# BMS-S02-V01-CellMonitor.net
KiCad netlist of a schematic drawn in Altium Designer
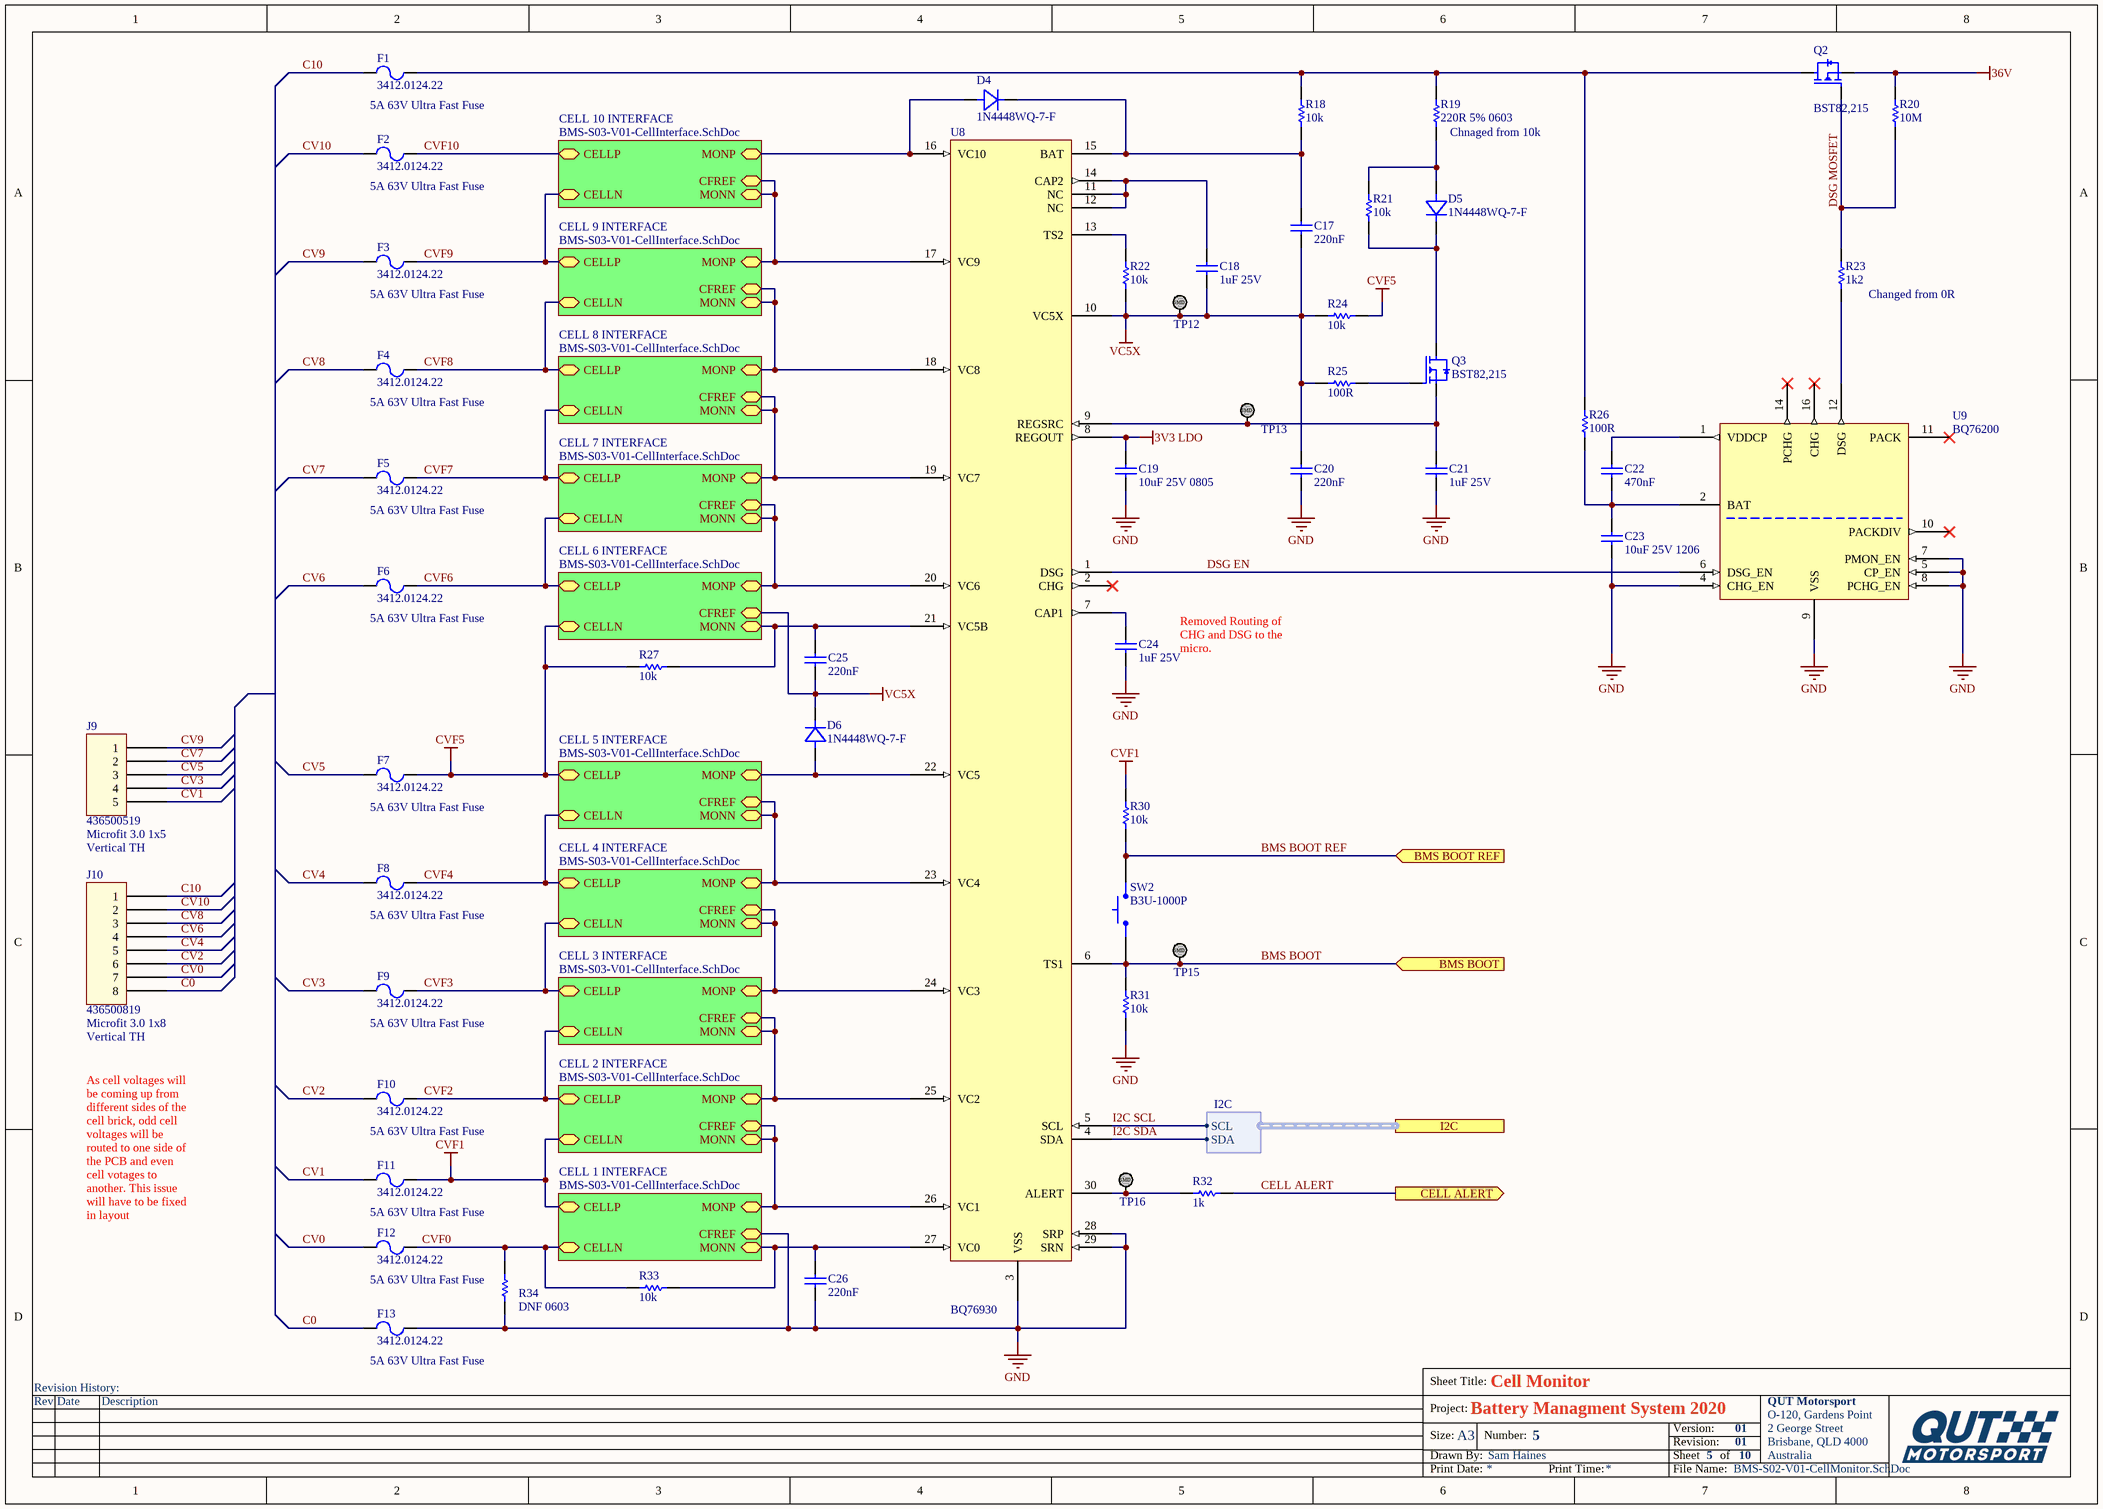
[diagram p0: BMS-S02-V01-CellMonitor.SchDoc]

(export (version "E")
  (design (tool "Eeschema 10.0.6"))
  (components
    (comp (ref "C17")
      (value "220nF")
      (footprint "Cap_Ceramic_0603")
      (description "Capacitor, Ceramic, SMD, 220nF, 50V, 5%, X7R, 0603")
      (libsource (lib "StandardCapacitors") (part "220nF 50V 5% X7R 0603"))
    )
    (comp (ref "C18")
      (value "1uF 25V")
      (footprint "Cap_Ceramic_0603")
      (description "Capacitor, Ceramic, SMD, 1uF, 25V, 5%, X7R, 0603")
      (libsource (lib "StandardCapacitors") (part "1uF 25V 5% X7R 0603"))
    )
    (comp (ref "C19")
      (value "10uF 25V 0805")
      (footprint "Cap_Ceramic_0805")
      (description "Capacitor, Ceramic, SMD, 10uF, 25V, 5%, X7R, 0805")
      (libsource (lib "StandardCapacitors") (part "10uF 25V 5% X7R 0805_1"))
    )
    (comp (ref "C20")
      (value "220nF")
      (footprint "Cap_Ceramic_0603")
      (description "Capacitor, Ceramic, SMD, 220nF, 50V, 5%, X7R, 0603")
      (libsource (lib "StandardCapacitors") (part "220nF 50V 5% X7R 0603"))
    )
    (comp (ref "C21")
      (value "1uF 25V")
      (footprint "Cap_Ceramic_0603")
      (description "Capacitor, Ceramic, SMD, 1uF, 25V, 5%, X7R, 0603")
      (libsource (lib "StandardCapacitors") (part "1uF 25V 5% X7R 0603"))
    )
    (comp (ref "C22")
      (value "470nF")
      (footprint "Cap_Ceramic_0603")
      (description "Capacitor, Ceramic, SMD, 470nF, 50V, 5%, X7R, 0603")
      (libsource (lib "StandardCapacitors") (part "470nF 50V 5% X7R 0603"))
    )
    (comp (ref "C23")
      (value "10uF 25V 1206")
      (footprint "Cap_Ceramic_1206")
      (description "Capacitor, Ceramic, SMD, 10uF, 25V, 10%, X7R, 1206")
      (libsource (lib "StandardCapacitors") (part "10uF 25V 10% X7R 1206"))
    )
    (comp (ref "C24")
      (value "1uF 25V")
      (footprint "Cap_Ceramic_0603")
      (description "Capacitor, Ceramic, SMD, 1uF, 25V, 5%, X7R, 0603")
      (libsource (lib "StandardCapacitors") (part "1uF 25V 5% X7R 0603"))
    )
    (comp (ref "C25")
      (value "220nF")
      (footprint "Cap_Ceramic_0603")
      (description "Capacitor, Ceramic, SMD, 220nF, 50V, 5%, X7R, 0603")
      (libsource (lib "StandardCapacitors") (part "220nF 50V 5% X7R 0603"))
    )
    (comp (ref "C26")
      (value "220nF")
      (footprint "Cap_Ceramic_0603")
      (description "Capacitor, Ceramic, SMD, 220nF, 50V, 5%, X7R, 0603")
      (libsource (lib "StandardCapacitors") (part "220nF 50V 5% X7R 0603"))
    )
    (comp (ref "D4")
      (value "1N4448WQ-7-F")
      (footprint "SMA")
      (description "Diode, SMD, 75V, 5%, 250mA, SOD123")
      (fields
        (field (name "MANUFACTURER") "ON Semiconductor / Fairchild")
        (field (name "MANUFACTURER PART NUMBER") "1N914BWS")
      )
      (libsource (lib "QUTMS_DiodeLibrary") (part "1N4448WQ-7-F"))
    )
    (comp (ref "D5")
      (value "1N4448WQ-7-F")
      (footprint "SMA")
      (description "Diode, SMD, 75V, 5%, 250mA, SOD123")
      (fields
        (field (name "MANUFACTURER") "ON Semiconductor / Fairchild")
        (field (name "MANUFACTURER PART NUMBER") "1N914BWS")
      )
      (libsource (lib "QUTMS_DiodeLibrary") (part "1N4448WQ-7-F"))
    )
    (comp (ref "D6")
      (value "1N4448WQ-7-F")
      (footprint "SMA")
      (description "Diode, SMD, 75V, 5%, 250mA, SOD123")
      (fields
        (field (name "MANUFACTURER") "ON Semiconductor / Fairchild")
        (field (name "MANUFACTURER PART NUMBER") "1N914BWS")
      )
      (libsource (lib "QUTMS_DiodeLibrary") (part "1N4448WQ-7-F"))
    )
    (comp (ref "F1")
      (value "3412.0124.22")
      (footprint "3412.0124.22")
      (description "FUSE BOARD MOUNT 5A 63VDC 0603")
      (libsource (lib "CellMonitor") (part "3412.0124.22"))
    )
    (comp (ref "F2")
      (value "3412.0124.22")
      (footprint "3412.0124.22")
      (description "FUSE BOARD MOUNT 5A 63VDC 0603")
      (libsource (lib "CellMonitor") (part "3412.0124.22"))
    )
    (comp (ref "F3")
      (value "3412.0124.22")
      (footprint "3412.0124.22")
      (description "FUSE BOARD MOUNT 5A 63VDC 0603")
      (libsource (lib "CellMonitor") (part "3412.0124.22"))
    )
    (comp (ref "F4")
      (value "3412.0124.22")
      (footprint "3412.0124.22")
      (description "FUSE BOARD MOUNT 5A 63VDC 0603")
      (libsource (lib "CellMonitor") (part "3412.0124.22"))
    )
    (comp (ref "F5")
      (value "3412.0124.22")
      (footprint "3412.0124.22")
      (description "FUSE BOARD MOUNT 5A 63VDC 0603")
      (libsource (lib "CellMonitor") (part "3412.0124.22"))
    )
    (comp (ref "F6")
      (value "3412.0124.22")
      (footprint "3412.0124.22")
      (description "FUSE BOARD MOUNT 5A 63VDC 0603")
      (libsource (lib "CellMonitor") (part "3412.0124.22"))
    )
    (comp (ref "F7")
      (value "3412.0124.22")
      (footprint "3412.0124.22")
      (description "FUSE BOARD MOUNT 5A 63VDC 0603")
      (libsource (lib "CellMonitor") (part "3412.0124.22"))
    )
    (comp (ref "F8")
      (value "3412.0124.22")
      (footprint "3412.0124.22")
      (description "FUSE BOARD MOUNT 5A 63VDC 0603")
      (libsource (lib "CellMonitor") (part "3412.0124.22"))
    )
    (comp (ref "F9")
      (value "3412.0124.22")
      (footprint "3412.0124.22")
      (description "FUSE BOARD MOUNT 5A 63VDC 0603")
      (libsource (lib "CellMonitor") (part "3412.0124.22"))
    )
    (comp (ref "F10")
      (value "3412.0124.22")
      (footprint "3412.0124.22")
      (description "FUSE BOARD MOUNT 5A 63VDC 0603")
      (libsource (lib "CellMonitor") (part "3412.0124.22"))
    )
    (comp (ref "F11")
      (value "3412.0124.22")
      (footprint "3412.0124.22")
      (description "FUSE BOARD MOUNT 5A 63VDC 0603")
      (libsource (lib "CellMonitor") (part "3412.0124.22"))
    )
    (comp (ref "F12")
      (value "3412.0124.22")
      (footprint "3412.0124.22")
      (description "FUSE BOARD MOUNT 5A 63VDC 0603")
      (libsource (lib "CellMonitor") (part "3412.0124.22"))
    )
    (comp (ref "F13")
      (value "3412.0124.22")
      (footprint "3412.0124.22")
      (description "FUSE BOARD MOUNT 5A 63VDC 0603")
      (libsource (lib "CellMonitor") (part "3412.0124.22"))
    )
    (comp (ref "J9")
      (value "436500519")
      (footprint "Microfit_1X5_V_TH")
      (libsource (lib "QUTMS_MicrofitLibrary") (part "Microfit_1x5"))
    )
    (comp (ref "J10")
      (value "436500819")
      (footprint "Microfit_1X8_V_TH")
      (libsource (lib "QUTMS_MicrofitLibrary") (part "Microfit_1x8"))
    )
    (comp (ref "Q2")
      (value "BST82,215")
      (footprint "BST82,215")
      (description "MOSFET N-CH, 20V, SOT23\r\nAlternate Part\r\n2N7002LT1G0SCT-ND")
      (libsource (lib "") (part "BST82,215_1"))
    )
    (comp (ref "Q3")
      (value "BST82,215")
      (footprint "BST82,215")
      (description "MOSFET N-CH, 20V, SOT23")
      (libsource (lib "CellMonitor") (part "BST82,215"))
    )
    (comp (ref "R18")
      (value "10k")
      (footprint "Res_ThinFilm_0603")
      (description "Resistor, SMD, 10k, 0.1W, 5%, 0603")
      (libsource (lib "StandardResistors") (part "10k 5% 0603"))
    )
    (comp (ref "R19")
      (value "220R 5% 0603")
      (footprint "Res_ThinFilm_0603")
      (description "Resistor, SMD, 220R, 0.1W, 5%, 0603")
      (libsource (lib "StandardResistors") (part "470R 5% 0603"))
    )
    (comp (ref "R20")
      (value "10M")
      (footprint "Res_ThinFilm_0603")
      (description "Resistor, SMD, 10M, 0.1W, 5%, 0603")
      (libsource (lib "StandardResistors") (part "10M 5% 0603"))
    )
    (comp (ref "R21")
      (value "10k")
      (footprint "Res_ThinFilm_0603")
      (description "Resistor, SMD, 10k, 0.1W, 5%, 0603")
      (libsource (lib "StandardResistors") (part "10k 5% 0603"))
    )
    (comp (ref "R22")
      (value "10k")
      (footprint "Res_ThinFilm_0603")
      (description "Resistor, SMD, 10k, 0.1W, 5%, 0603")
      (libsource (lib "StandardResistors") (part "10k 5% 0603"))
    )
    (comp (ref "R23")
      (value "1k2")
      (footprint "Res_ThinFilm_0603")
      (description "Resistor, SMD, 1k2R, 0.1W, 5%, 0603")
      (libsource (lib "StandardResistors") (part "0R 5% 0603"))
    )
    (comp (ref "R24")
      (value "10k")
      (footprint "Res_ThinFilm_0603")
      (description "Resistor, SMD, 10k, 0.1W, 5%, 0603")
      (libsource (lib "StandardResistors") (part "10k 5% 0603"))
    )
    (comp (ref "R25")
      (value "100R")
      (footprint "Res_ThinFilm_0603")
      (description "Resistor, SMD, 100R, 0.1W, 5%, 0603")
      (libsource (lib "StandardResistors") (part "100R 5%, 0603"))
    )
    (comp (ref "R26")
      (value "100R")
      (footprint "Res_ThinFilm_0603")
      (description "Resistor, SMD, 100R, 0.1W, 5%, 0603")
      (libsource (lib "StandardResistors") (part "100R 5%, 0603"))
    )
    (comp (ref "R27")
      (value "10k")
      (footprint "Res_ThinFilm_0603")
      (description "Resistor, SMD, 10k, 0.1W, 5%, 0603")
      (libsource (lib "StandardResistors") (part "10k 5% 0603"))
    )
    (comp (ref "R30")
      (value "10k")
      (footprint "Res_ThinFilm_0603")
      (description "Resistor, SMD, 10k, 0.1W, 5%, 0603")
      (libsource (lib "StandardResistors") (part "10k 5% 0603"))
    )
    (comp (ref "R31")
      (value "10k")
      (footprint "Res_ThinFilm_0603")
      (description "Resistor, SMD, 10k, 0.1W, 5%, 0603")
      (libsource (lib "StandardResistors") (part "10k 5% 0603"))
    )
    (comp (ref "R32")
      (value "1k")
      (footprint "Res_ThinFilm_0603")
      (description "Resistor, SMD, 1k, 0.1W, 5%, 0603")
      (libsource (lib "StandardResistors") (part "1k 5% 0603"))
    )
    (comp (ref "R33")
      (value "10k")
      (footprint "Res_ThinFilm_0603")
      (description "Resistor, SMD, 10k, 0.1W, 5%, 0603")
      (libsource (lib "StandardResistors") (part "10k 5% 0603"))
    )
    (comp (ref "R34")
      (value "DNF 0603")
      (footprint "Res_ThinFilm_0603")
      (description "Resistor, SMD, DNF, 0.1W, 0603")
      (libsource (lib "StandardResistors") (part "DNF 0603"))
    )
    (comp (ref "SW2")
      (value "B3U-1000P")
      (footprint "BTN B3U-1000P")
      (description "Omron B3U-1000P Ultra Miniture Switch")
      (libsource (lib "QUTMS_SwitchLibrary") (part "BTN B3U-1000P"))
    )
    (comp (ref "TP12")
      (value "TestPoint_SMD")
      (footprint "TestPointSMD")
      (libsource (lib "StandardTest") (part "TestPoint_SMD"))
    )
    (comp (ref "TP13")
      (value "TestPoint_SMD")
      (footprint "TestPointSMD")
      (libsource (lib "StandardTest") (part "TestPoint_SMD"))
    )
    (comp (ref "TP15")
      (value "TestPoint_SMD")
      (footprint "TestPointSMD")
      (libsource (lib "StandardTest") (part "TestPoint_SMD"))
    )
    (comp (ref "TP16")
      (value "TestPoint_SMD")
      (footprint "TestPointSMD")
      (libsource (lib "StandardTest") (part "TestPoint_SMD"))
    )
    (comp (ref "U8")
      (value "BQ76930")
      (footprint "bq76930")
      (description "Battery Monitoring/Fuel Gauge Li-Ion/Li-Polymer/LiFePO4 0V to 16V 30-Pin TSSOP T/R")
      (fields (field (name "INTERNALPART") "Test1234") (field (name "MANUFACTURER") "Texas Instruments"))
      (libsource (lib "CellMonitor") (part "BQ76930"))
    )
    (comp (ref "U9")
      (value "BQ76200")
      (footprint "BQ76200")
      (description "High-voltage battery pack front-end charge/discharge high-side NFET driver")
      (fields (field (name "MPN") "BQ76200PWR") (field (name "MANUFACTURER") "Texas Instruments"))
      (libsource (lib "CellMonitor") (part "BQ76200PWR"))
    )
  )
  (nets
    (net (code "2") (name "/BMS BOOT") (class "Default")
      (node (ref "R31") (pin "2") (pinfunction "2_2") (pintype "passive"))
      (node (ref "SW2") (pin "1") (pinfunction "1_1") (pintype "passive"))
      (node (ref "TP15") (pin "1") (pinfunction "1_1") (pintype "passive"))
      (node (ref "U8") (pin "6") (pinfunction "TS1_6") (pintype "passive"))
    )
    (net (code "3") (name "/BMS BOOT REF") (class "Default")
      (node (ref "R30") (pin "1") (pinfunction "1_1") (pintype "passive"))
      (node (ref "SW2") (pin "2") (pinfunction "2_2") (pintype "passive"))
    )
    (net (code "4") (name "/C0") (class "Default")
      (node (ref "F13") (pin "1") (pinfunction "1_1") (pintype "passive"))
      (node (ref "J10") (pin "8") (pinfunction "8_8") (pintype "passive"))
    )
    (net (code "5") (name "/C10") (class "Default")
      (node (ref "F1") (pin "1") (pinfunction "1_1") (pintype "passive"))
      (node (ref "J10") (pin "1") (pinfunction "1_1") (pintype "passive"))
    )
    (net (code "6") (name "/CELL ALERT") (class "Default")
      (node (ref "R32") (pin "2") (pinfunction "2_2") (pintype "passive"))
    )
    (net (code "7") (name "/CFREF") (class "Default")
      (node (ref "U8") (pin "17") (pinfunction "VC9_17") (pintype "input"))
    )
    (net (code "8") (name "/CFREF_1") (class "Default")
      (node (ref "U8") (pin "26") (pinfunction "VC1_26") (pintype "input"))
    )
    (net (code "9") (name "/CFREF_2") (class "Default")
      (node (ref "U8") (pin "23") (pinfunction "VC4_23") (pintype "input"))
    )
    (net (code "10") (name "/CFREF_3") (class "Default")
      (node (ref "U8") (pin "25") (pinfunction "VC2_25") (pintype "input"))
    )
    (net (code "11") (name "/CFREF_4") (class "Default")
      (node (ref "U8") (pin "24") (pinfunction "VC3_24") (pintype "input"))
    )
    (net (code "12") (name "/CFREF_5") (class "Default")
      (node (ref "U8") (pin "18") (pinfunction "VC8_18") (pintype "input"))
    )
    (net (code "13") (name "/CFREF_6") (class "Default")
      (node (ref "U8") (pin "19") (pinfunction "VC7_19") (pintype "input"))
    )
    (net (code "14") (name "/CFREF_7") (class "Default")
      (node (ref "U8") (pin "20") (pinfunction "VC6_20") (pintype "input"))
    )
    (net (code "15") (name "/CV0") (class "Default")
      (node (ref "F12") (pin "1") (pinfunction "1_1") (pintype "passive"))
      (node (ref "J10") (pin "7") (pinfunction "7_7") (pintype "passive"))
    )
    (net (code "16") (name "/CV1") (class "Default")
      (node (ref "F11") (pin "1") (pinfunction "1_1") (pintype "passive"))
      (node (ref "J9") (pin "5") (pinfunction "5_5") (pintype "passive"))
    )
    (net (code "17") (name "/CV2") (class "Default")
      (node (ref "F10") (pin "1") (pinfunction "1_1") (pintype "passive"))
      (node (ref "J10") (pin "6") (pinfunction "6_6") (pintype "passive"))
    )
    (net (code "18") (name "/CV3") (class "Default")
      (node (ref "F9") (pin "1") (pinfunction "1_1") (pintype "passive"))
      (node (ref "J9") (pin "4") (pinfunction "4_4") (pintype "passive"))
    )
    (net (code "19") (name "/CV4") (class "Default")
      (node (ref "F8") (pin "1") (pinfunction "1_1") (pintype "passive"))
      (node (ref "J10") (pin "5") (pinfunction "5_5") (pintype "passive"))
    )
    (net (code "20") (name "/CV5") (class "Default")
      (node (ref "F7") (pin "1") (pinfunction "1_1") (pintype "passive"))
      (node (ref "J9") (pin "3") (pinfunction "3_3") (pintype "passive"))
    )
    (net (code "21") (name "/CV6") (class "Default")
      (node (ref "F6") (pin "1") (pinfunction "1_1") (pintype "passive"))
      (node (ref "J10") (pin "4") (pinfunction "4_4") (pintype "passive"))
    )
    (net (code "22") (name "/CV7") (class "Default")
      (node (ref "F5") (pin "1") (pinfunction "1_1") (pintype "passive"))
      (node (ref "J9") (pin "2") (pinfunction "2_2") (pintype "passive"))
    )
    (net (code "23") (name "/CV8") (class "Default")
      (node (ref "F4") (pin "1") (pinfunction "1_1") (pintype "passive"))
      (node (ref "J10") (pin "3") (pinfunction "3_3") (pintype "passive"))
    )
    (net (code "24") (name "/CV9") (class "Default")
      (node (ref "F3") (pin "1") (pinfunction "1_1") (pintype "passive"))
      (node (ref "J9") (pin "1") (pinfunction "1_1") (pintype "passive"))
    )
    (net (code "25") (name "/CV10") (class "Default")
      (node (ref "F2") (pin "1") (pinfunction "1_1") (pintype "passive"))
      (node (ref "J10") (pin "2") (pinfunction "2_2") (pintype "passive"))
    )
    (net (code "26") (name "/CVF0") (class "Default")
      (node (ref "F12") (pin "2") (pinfunction "2_2") (pintype "passive"))
      (node (ref "R33") (pin "1") (pinfunction "1_1") (pintype "passive"))
      (node (ref "R34") (pin "2") (pinfunction "2_2") (pintype "passive"))
    )
    (net (code "27") (name "/CVF2") (class "Default")
      (node (ref "F10") (pin "2") (pinfunction "2_2") (pintype "passive"))
    )
    (net (code "28") (name "/CVF3") (class "Default")
      (node (ref "F9") (pin "2") (pinfunction "2_2") (pintype "passive"))
    )
    (net (code "29") (name "/CVF4") (class "Default")
      (node (ref "F8") (pin "2") (pinfunction "2_2") (pintype "passive"))
    )
    (net (code "30") (name "/CVF6") (class "Default")
      (node (ref "F6") (pin "2") (pinfunction "2_2") (pintype "passive"))
    )
    (net (code "31") (name "/CVF7") (class "Default")
      (node (ref "F5") (pin "2") (pinfunction "2_2") (pintype "passive"))
    )
    (net (code "32") (name "/CVF8") (class "Default")
      (node (ref "F4") (pin "2") (pinfunction "2_2") (pintype "passive"))
    )
    (net (code "33") (name "/CVF9") (class "Default")
      (node (ref "F3") (pin "2") (pinfunction "2_2") (pintype "passive"))
    )
    (net (code "34") (name "/CVF10") (class "Default")
      (node (ref "F2") (pin "2") (pinfunction "2_2") (pintype "passive"))
    )
    (net (code "35") (name "/DSG EN") (class "Default")
      (node (ref "U8") (pin "1") (pinfunction "DSG_1") (pintype "output"))
      (node (ref "U9") (pin "6") (pinfunction "DSG_EN_6") (pintype "input"))
    )
    (net (code "36") (name "/DSG MOSFET") (class "Default")
      (node (ref "Q2") (pin "G") (pinfunction "Gate_G") (pintype "passive"))
      (node (ref "R20") (pin "1") (pinfunction "1_1") (pintype "passive"))
      (node (ref "R23") (pin "2") (pinfunction "2_2") (pintype "passive"))
    )
    (net (code "37") (name "/I2C SCL") (class "Default")
      (node (ref "U8") (pin "5") (pinfunction "SCL_5") (pintype "input"))
    )
    (net (code "38") (name "/I2C SDA") (class "Default")
      (node (ref "U8") (pin "4") (pinfunction "SDA_4") (pintype "passive"))
    )
    (net (code "39") (name "/MONN") (class "Default")
      (node (ref "C25") (pin "2") (pinfunction "2_2") (pintype "passive"))
      (node (ref "R27") (pin "2") (pinfunction "2_2") (pintype "passive"))
      (node (ref "U8") (pin "21") (pinfunction "VC5B_21") (pintype "input"))
    )
    (net (code "40") (name "/MONN_1") (class "Default")
      (node (ref "C26") (pin "2") (pinfunction "2_2") (pintype "passive"))
      (node (ref "R33") (pin "2") (pinfunction "2_2") (pintype "passive"))
      (node (ref "U8") (pin "27") (pinfunction "VC0_27") (pintype "input"))
    )
    (net (code "41") (name "/MONP") (class "Default")
      (node (ref "D4") (pin "A") (pinfunction "Anode_A") (pintype "passive"))
      (node (ref "U8") (pin "16") (pinfunction "VC10_16") (pintype "input"))
    )
    (net (code "42") (name "/MONP_1") (class "Default")
      (node (ref "D6") (pin "A") (pinfunction "Anode_A") (pintype "passive"))
      (node (ref "U8") (pin "22") (pinfunction "VC5_22") (pintype "input"))
    )
    (net (code "44") (name "3V3 LDO") (class "Default")
      (node (ref "C19") (pin "2") (pinfunction "2_2") (pintype "passive"))
      (node (ref "U8") (pin "8") (pinfunction "REGOUT_8") (pintype "output"))
    )
    (net (code "45") (name "36V") (class "Default")
      (node (ref "Q2") (pin "S") (pinfunction "Source_S") (pintype "passive"))
      (node (ref "R20") (pin "2") (pinfunction "2_2") (pintype "passive"))
    )
    (net (code "46") (name "CVF1") (class "Default")
      (node (ref "F11") (pin "2") (pinfunction "2_2") (pintype "passive"))
      (node (ref "R30") (pin "2") (pinfunction "2_2") (pintype "passive"))
    )
    (net (code "47") (name "CVF5") (class "Default")
      (node (ref "F7") (pin "2") (pinfunction "2_2") (pintype "passive"))
      (node (ref "R24") (pin "2") (pinfunction "2_2") (pintype "passive"))
      (node (ref "R27") (pin "1") (pinfunction "1_1") (pintype "passive"))
    )
    (net (code "48") (name "GND") (class "Default")
      (node (ref "C19") (pin "1") (pinfunction "1_1") (pintype "passive"))
      (node (ref "C20") (pin "1") (pinfunction "1_1") (pintype "passive"))
      (node (ref "C21") (pin "1") (pinfunction "1_1") (pintype "passive"))
      (node (ref "C23") (pin "1") (pinfunction "1_1") (pintype "passive"))
      (node (ref "C24") (pin "1") (pinfunction "1_1") (pintype "passive"))
      (node (ref "C26") (pin "1") (pinfunction "1_1") (pintype "passive"))
      (node (ref "F13") (pin "2") (pinfunction "2_2") (pintype "passive"))
      (node (ref "R31") (pin "1") (pinfunction "1_1") (pintype "passive"))
      (node (ref "R34") (pin "1") (pinfunction "1_1") (pintype "passive"))
      (node (ref "U8") (pin "28") (pinfunction "SRP_28") (pintype "input"))
      (node (ref "U8") (pin "29") (pinfunction "SRN_29") (pintype "input"))
      (node (ref "U8") (pin "3") (pinfunction "VSS_3") (pintype "power_in"))
      (node (ref "U9") (pin "4") (pinfunction "CHG_EN_4") (pintype "input"))
      (node (ref "U9") (pin "5") (pinfunction "CP_EN_5") (pintype "input"))
      (node (ref "U9") (pin "7") (pinfunction "PMON_EN_7") (pintype "input"))
      (node (ref "U9") (pin "8") (pinfunction "PCHG_EN_8") (pintype "input"))
      (node (ref "U9") (pin "9") (pinfunction "VSS_9") (pintype "passive"))
    )
    (net (code "49") (name "Net-(D4-Cathode)") (class "Default")
      (node (ref "C17") (pin "2") (pinfunction "2_2") (pintype "passive"))
      (node (ref "D4") (pin "K") (pinfunction "Cathode_K") (pintype "passive"))
      (node (ref "R18") (pin "1") (pinfunction "1_1") (pintype "passive"))
      (node (ref "U8") (pin "15") (pinfunction "BAT_15") (pintype "power_in"))
    )
    (net (code "50") (name "Net-(D5-Anode)") (class "Default")
      (node (ref "D5") (pin "A") (pinfunction "Anode_A") (pintype "passive"))
      (node (ref "R19") (pin "1") (pinfunction "1_1") (pintype "passive"))
      (node (ref "R21") (pin "2") (pinfunction "2_2") (pintype "passive"))
    )
    (net (code "51") (name "Net-(D5-Cathode)") (class "Default")
      (node (ref "D5") (pin "K") (pinfunction "Cathode_K") (pintype "passive"))
      (node (ref "Q3") (pin "D") (pinfunction "Drain_D") (pintype "passive"))
      (node (ref "R21") (pin "1") (pinfunction "1_1") (pintype "passive"))
    )
    (net (code "52") (name "Net-(Q2-Drain)") (class "Default")
      (node (ref "F1") (pin "2") (pinfunction "2_2") (pintype "passive"))
      (node (ref "Q2") (pin "D") (pinfunction "Drain_D") (pintype "passive"))
      (node (ref "R18") (pin "2") (pinfunction "2_2") (pintype "passive"))
      (node (ref "R19") (pin "2") (pinfunction "2_2") (pintype "passive"))
      (node (ref "R26") (pin "2") (pinfunction "2_2") (pintype "passive"))
    )
    (net (code "53") (name "Net-(Q3-Gate)") (class "Default")
      (node (ref "Q3") (pin "G") (pinfunction "Gate_G") (pintype "passive"))
      (node (ref "R25") (pin "1") (pinfunction "1_1") (pintype "passive"))
    )
    (net (code "54") (name "Net-(Q3-Source)") (class "Default")
      (node (ref "C21") (pin "2") (pinfunction "2_2") (pintype "passive"))
      (node (ref "Q3") (pin "S") (pinfunction "Source_S") (pintype "passive"))
      (node (ref "TP13") (pin "1") (pinfunction "1_1") (pintype "passive"))
      (node (ref "U8") (pin "9") (pinfunction "REGSRC_9") (pintype "input"))
    )
    (net (code "55") (name "Net-(U8-ALERT)") (class "Default")
      (node (ref "R32") (pin "1") (pinfunction "1_1") (pintype "passive"))
      (node (ref "TP16") (pin "1") (pinfunction "1_1") (pintype "passive"))
      (node (ref "U8") (pin "30") (pinfunction "ALERT_30") (pintype "passive"))
    )
    (net (code "56") (name "Net-(U8-CAP1)") (class "Default")
      (node (ref "C24") (pin "2") (pinfunction "2_2") (pintype "passive"))
      (node (ref "U8") (pin "7") (pinfunction "CAP1_7") (pintype "output"))
    )
    (net (code "57") (name "Net-(U8-CAP2)") (class "Default")
      (node (ref "C18") (pin "2") (pinfunction "2_2") (pintype "passive"))
      (node (ref "U8") (pin "11") (pinfunction "NC_11") (pintype "power_in"))
      (node (ref "U8") (pin "12") (pinfunction "NC_12") (pintype "power_in"))
      (node (ref "U8") (pin "14") (pinfunction "CAP2_14") (pintype "output"))
    )
    (net (code "58") (name "Net-(U8-TS2)") (class "Default")
      (node (ref "R22") (pin "2") (pinfunction "2_2") (pintype "passive"))
      (node (ref "U8") (pin "13") (pinfunction "TS2_13") (pintype "passive"))
    )
    (net (code "59") (name "Net-(U9-BAT)") (class "Default")
      (node (ref "C22") (pin "1") (pinfunction "1_1") (pintype "passive"))
      (node (ref "C23") (pin "2") (pinfunction "2_2") (pintype "passive"))
      (node (ref "R26") (pin "1") (pinfunction "1_1") (pintype "passive"))
      (node (ref "U9") (pin "2") (pinfunction "BAT_2") (pintype "passive"))
    )
    (net (code "60") (name "Net-(U9-DSG)") (class "Default")
      (node (ref "R23") (pin "1") (pinfunction "1_1") (pintype "passive"))
      (node (ref "U9") (pin "12") (pinfunction "DSG_12") (pintype "output"))
    )
    (net (code "61") (name "Net-(U9-VDDCP)") (class "Default")
      (node (ref "C22") (pin "2") (pinfunction "2_2") (pintype "passive"))
      (node (ref "U9") (pin "1") (pinfunction "VDDCP_1") (pintype "output"))
    )
    (net (code "62") (name "VC5X") (class "Default")
      (node (ref "C17") (pin "1") (pinfunction "1_1") (pintype "passive"))
      (node (ref "C18") (pin "1") (pinfunction "1_1") (pintype "passive"))
      (node (ref "C20") (pin "2") (pinfunction "2_2") (pintype "passive"))
      (node (ref "C25") (pin "1") (pinfunction "1_1") (pintype "passive"))
      (node (ref "D6") (pin "K") (pinfunction "Cathode_K") (pintype "passive"))
      (node (ref "R22") (pin "1") (pinfunction "1_1") (pintype "passive"))
      (node (ref "R24") (pin "1") (pinfunction "1_1") (pintype "passive"))
      (node (ref "R25") (pin "2") (pinfunction "2_2") (pintype "passive"))
      (node (ref "TP12") (pin "1") (pinfunction "1_1") (pintype "passive"))
      (node (ref "U8") (pin "10") (pinfunction "VC5X_10") (pintype "power_in"))
    )
    (net (code "63") (name "unconnected-(U8-CHG-Pad2)") (class "Default")
      (node (ref "U8") (pin "2") (pinfunction "CHG_2") (pintype "output+no_connect"))
    )
    (net (code "64") (name "unconnected-(U9-CHG-Pad16)") (class "Default")
      (node (ref "U9") (pin "16") (pinfunction "CHG_16") (pintype "output+no_connect"))
    )
    (net (code "65") (name "unconnected-(U9-PACK-Pad11)") (class "Default")
      (node (ref "U9") (pin "11") (pinfunction "PACK_11") (pintype "passive+no_connect"))
    )
    (net (code "66") (name "unconnected-(U9-PACKDIV-Pad10)") (class "Default")
      (node (ref "U9") (pin "10") (pinfunction "PACKDIV_10") (pintype "output+no_connect"))
    )
    (net (code "67") (name "unconnected-(U9-PCHG-Pad14)") (class "Default")
      (node (ref "U9") (pin "14") (pinfunction "PCHG_14") (pintype "output+no_connect"))
    )
  )
)
